# Eagle_SoundSensor.net
KiCad netlist of a schematic drawn in EAGLE
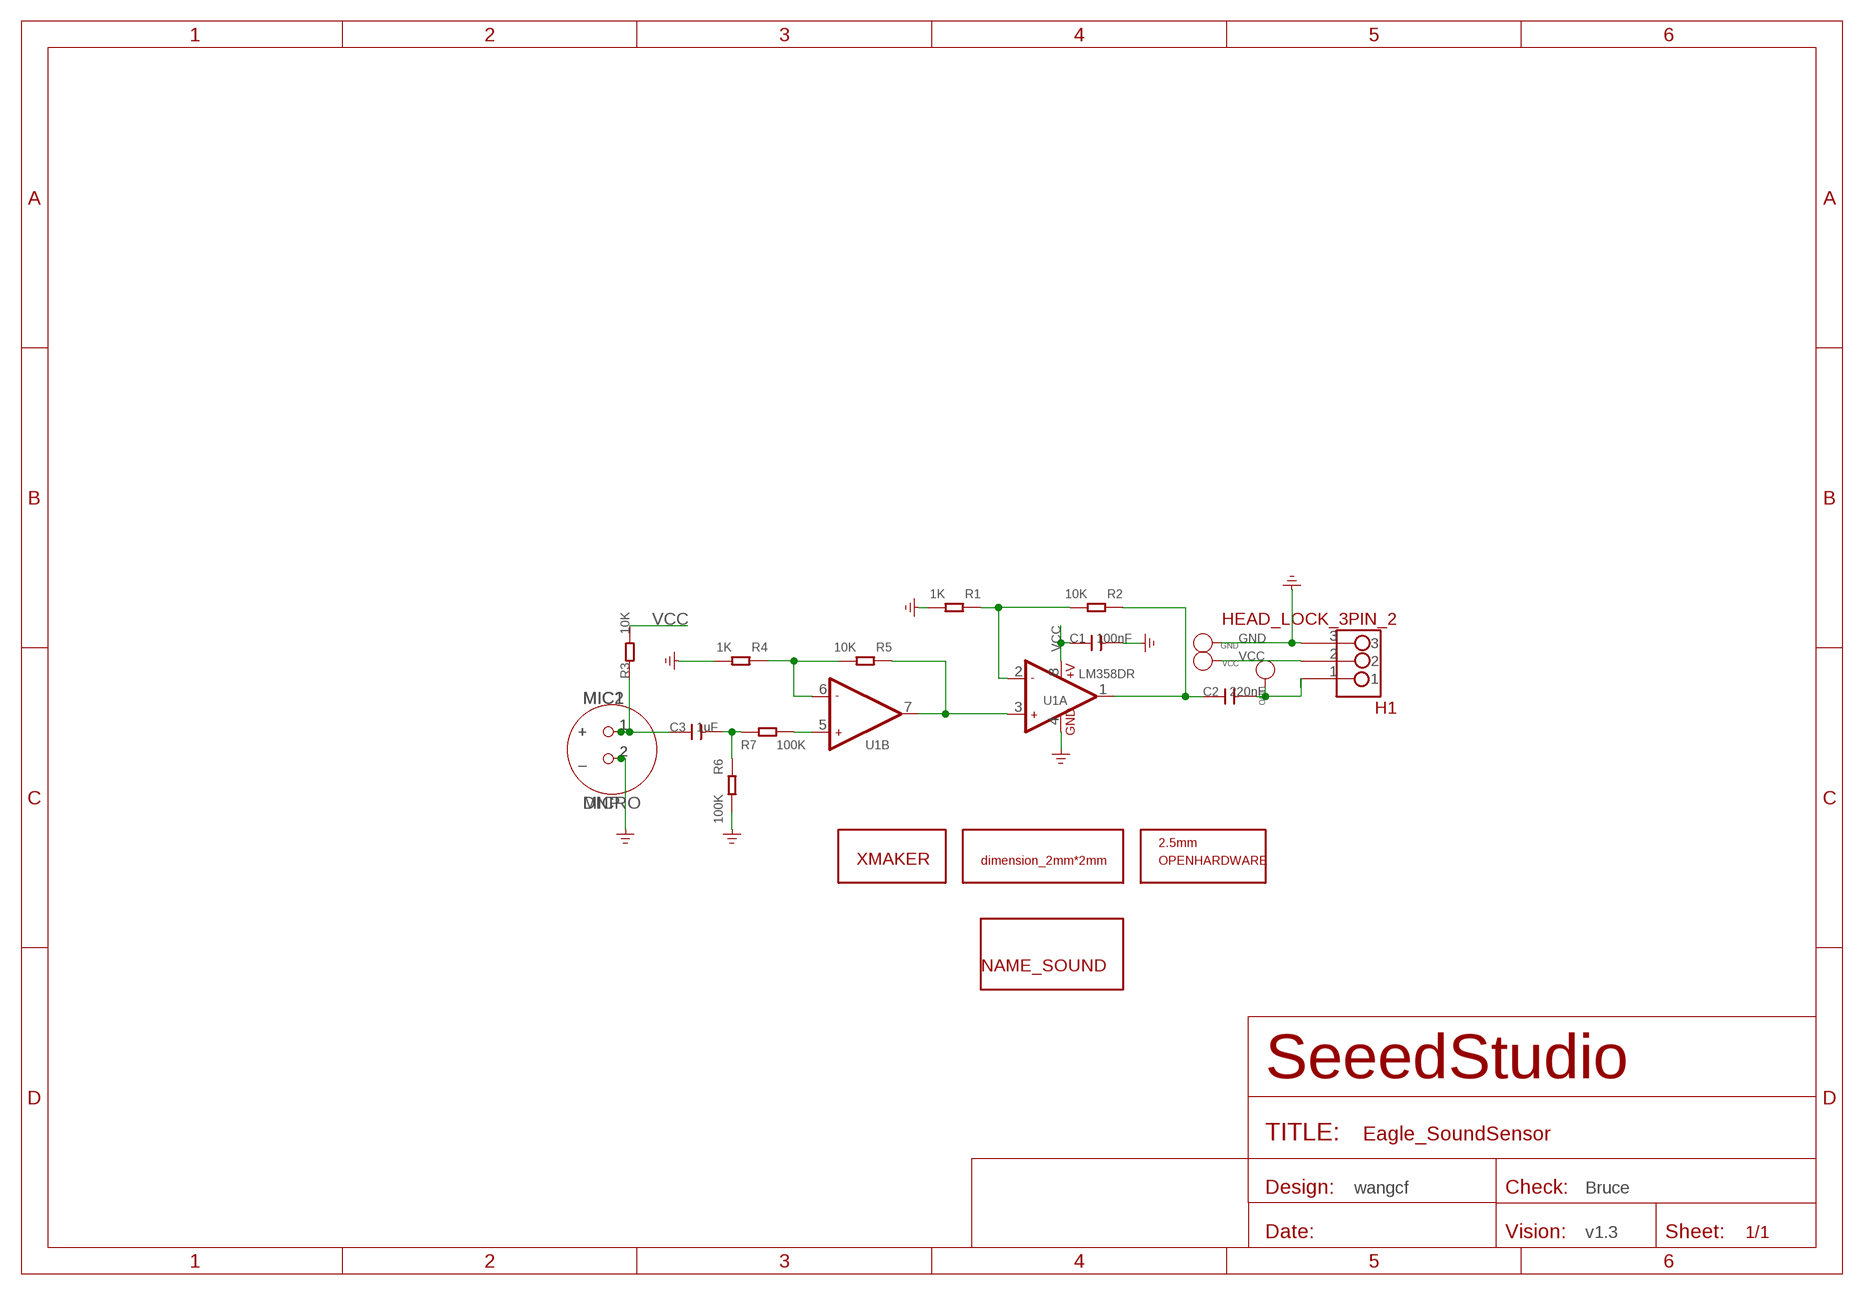
[diagram p0: schematic, sheet 1]

(export (version "E")
  (design (tool "Eeschema 10.0.6"))
  (components
    (comp (ref "C1")
      (value "100nF")
      (footprint "eagle-import:C0603")
      (libsource (lib "eagle-import") (part "C-0603"))
    )
    (comp (ref "C2")
      (value "220nF")
      (footprint "eagle-import:C0603")
      (libsource (lib "eagle-import") (part "C-0603"))
    )
    (comp (ref "C3")
      (value "1uF")
      (footprint "eagle-import:C0603")
      (libsource (lib "eagle-import") (part "C-0603"))
    )
    (comp (ref "GND")
      (value "PAD-TEST-POINT'4545'")
      (footprint "eagle-import:TP_4545")
      (fields (field (name "PARTNO") "DNP"))
      (libsource (lib "eagle-import") (part "PAD-TEST-POINT'4545'"))
    )
    (comp (ref "H1")
      (value "HEAD_LOCK_3PIN_2")
      (footprint "eagle-import:HEAD_LOCK_3PIN_2")
      (libsource (lib "eagle-import") (part "HEAD_LOCK_3PIN_2"))
    )
    (comp (ref "MIC1")
      (value "MICRO")
      (footprint "eagle-import:MICRO")
      (libsource (lib "eagle-import") (part "MICRO"))
    )
    (comp (ref "MIC2")
      (value "DNP")
      (footprint "eagle-import:MICRO")
      (libsource (lib "eagle-import") (part "MICRO"))
    )
    (comp (ref "OUT")
      (value "PAD-TEST-POINT'4545'")
      (footprint "eagle-import:TP_4545")
      (fields (field (name "PARTNO") "DNP"))
      (libsource (lib "eagle-import") (part "PAD-TEST-POINT'4545'"))
    )
    (comp (ref "R1")
      (value "1K")
      (footprint "eagle-import:R0603")
      (libsource (lib "eagle-import") (part "R-0603"))
    )
    (comp (ref "R2")
      (value "10K")
      (footprint "eagle-import:R0603")
      (libsource (lib "eagle-import") (part "R-0603"))
    )
    (comp (ref "R3")
      (value "10K")
      (footprint "eagle-import:R0603")
      (libsource (lib "eagle-import") (part "R-0603"))
    )
    (comp (ref "R4")
      (value "1K")
      (footprint "eagle-import:R0603")
      (libsource (lib "eagle-import") (part "R-0603"))
    )
    (comp (ref "R5")
      (value "10K")
      (footprint "eagle-import:R0603")
      (libsource (lib "eagle-import") (part "R-0603"))
    )
    (comp (ref "R6")
      (value "100K")
      (footprint "eagle-import:R0603")
      (libsource (lib "eagle-import") (part "R-0603"))
    )
    (comp (ref "R7")
      (value "100K")
      (footprint "eagle-import:R0603")
      (libsource (lib "eagle-import") (part "R-0603"))
    )
    (comp (ref "U$7")
      (value "XMAKERLOGO")
      (footprint "eagle-import:XMAKERLOGO")
      (libsource (lib "eagle-import") (part "XMAKERLOGO"))
    )
    (comp (ref "U$11")
      (value "DIMENSION_2MM2MM")
      (footprint "eagle-import:DIMENSION_2MM_2MM")
      (libsource (lib "eagle-import") (part "DIMENSION_2MM2MM"))
    )
    (comp (ref "U$12")
      (value "OPENHARDWARE_2.5MM_TOP")
      (footprint "eagle-import:OPENSOURCELOGO_2.5MM")
      (libsource (lib "eagle-import") (part "OPENHARDWARE_2.5MM_TOP"))
    )
    (comp (ref "U$13")
      (value "NAME_SOUND")
      (footprint "eagle-import:NAME_SOUND")
      (libsource (lib "eagle-import") (part "NAME_SOUND"))
    )
    (comp (ref "U1")
      (value "LM358DR")
      (footprint "eagle-import:SO08")
      (libsource (lib "eagle-import") (part "LMV358D"))
    )
    (comp (ref "VCC")
      (value "PAD-TEST-POINT'4545'")
      (footprint "eagle-import:TP_4545")
      (fields (field (name "PARTNO") "DNP"))
      (libsource (lib "eagle-import") (part "PAD-TEST-POINT'4545'"))
    )
  )
  (nets
    (net (code "1") (name "/VCC") (class "Default")
      (node (ref "C1") (pin "1") (pinfunction "1_1") (pintype "passive"))
      (node (ref "H1") (pin "2") (pinfunction "2_2") (pintype "passive"))
      (node (ref "R3") (pin "2") (pinfunction "2_2") (pintype "passive"))
      (node (ref "U1") (pin "8") (pinfunction "+V_8") (pintype "power_in"))
      (node (ref "VCC") (pin "T") (pinfunction "T_T") (pintype "bidirectional"))
    )
    (net (code "2") (name "GND_POWER") (class "Default")
      (node (ref "C1") (pin "2") (pinfunction "2_2") (pintype "passive"))
      (node (ref "GND") (pin "T") (pinfunction "T_T") (pintype "bidirectional"))
      (node (ref "H1") (pin "3") (pinfunction "3_3") (pintype "passive"))
      (node (ref "MIC1") (pin "2") (pinfunction "__2") (pintype "bidirectional"))
      (node (ref "MIC2") (pin "2") (pinfunction "__2") (pintype "bidirectional"))
      (node (ref "R1") (pin "2") (pinfunction "2_2") (pintype "passive"))
      (node (ref "R4") (pin "2") (pinfunction "2_2") (pintype "passive"))
      (node (ref "R6") (pin "2") (pinfunction "2_2") (pintype "passive"))
      (node (ref "U1") (pin "4") (pinfunction "GND_4") (pintype "power_in"))
    )
    (net (code "3") (name "Net-(C2-Pad2)") (class "Default")
      (node (ref "C2") (pin "2") (pinfunction "2_2") (pintype "passive"))
      (node (ref "H1") (pin "1") (pinfunction "1_1") (pintype "passive"))
      (node (ref "OUT") (pin "T") (pinfunction "T_T") (pintype "bidirectional"))
    )
    (net (code "4") (name "Net-(C3-Pad2)") (class "Default")
      (node (ref "C3") (pin "2") (pinfunction "2_2") (pintype "passive"))
      (node (ref "R6") (pin "1") (pinfunction "1_1") (pintype "passive"))
      (node (ref "R7") (pin "1") (pinfunction "1_1") (pintype "passive"))
    )
    (net (code "5") (name "Net-(MIC1-+)") (class "Default")
      (node (ref "C3") (pin "1") (pinfunction "1_1") (pintype "passive"))
      (node (ref "MIC1") (pin "1") (pinfunction "+_1") (pintype "bidirectional"))
      (node (ref "MIC2") (pin "1") (pinfunction "+_1") (pintype "bidirectional"))
      (node (ref "R3") (pin "1") (pinfunction "1_1") (pintype "passive"))
    )
    (net (code "6") (name "Net-(U1A-+IN1)") (class "Default")
      (node (ref "R5") (pin "1") (pinfunction "1_1") (pintype "passive"))
      (node (ref "U1") (pin "3") (pinfunction "+IN1_3") (pintype "input"))
      (node (ref "U1") (pin "7") (pinfunction "OUT2_7") (pintype "output"))
    )
    (net (code "7") (name "Net-(U1A--IN1)") (class "Default")
      (node (ref "R1") (pin "1") (pinfunction "1_1") (pintype "passive"))
      (node (ref "R2") (pin "2") (pinfunction "2_2") (pintype "passive"))
      (node (ref "U1") (pin "2") (pinfunction "-IN1_2") (pintype "input"))
    )
    (net (code "8") (name "Net-(U1A-OUT1)") (class "Default")
      (node (ref "C2") (pin "1") (pinfunction "1_1") (pintype "passive"))
      (node (ref "R2") (pin "1") (pinfunction "1_1") (pintype "passive"))
      (node (ref "U1") (pin "1") (pinfunction "OUT1_1") (pintype "output"))
    )
    (net (code "9") (name "Net-(U1B-+IN2)") (class "Default")
      (node (ref "R7") (pin "2") (pinfunction "2_2") (pintype "passive"))
      (node (ref "U1") (pin "5") (pinfunction "+IN2_5") (pintype "input"))
    )
    (net (code "10") (name "Net-(U1B--IN2)") (class "Default")
      (node (ref "R4") (pin "1") (pinfunction "1_1") (pintype "passive"))
      (node (ref "R5") (pin "2") (pinfunction "2_2") (pintype "passive"))
      (node (ref "U1") (pin "6") (pinfunction "-IN2_6") (pintype "input"))
    )
  )
)
